# LDR_based_circuit.net
KiCad netlist of a schematic drawn in EAGLE
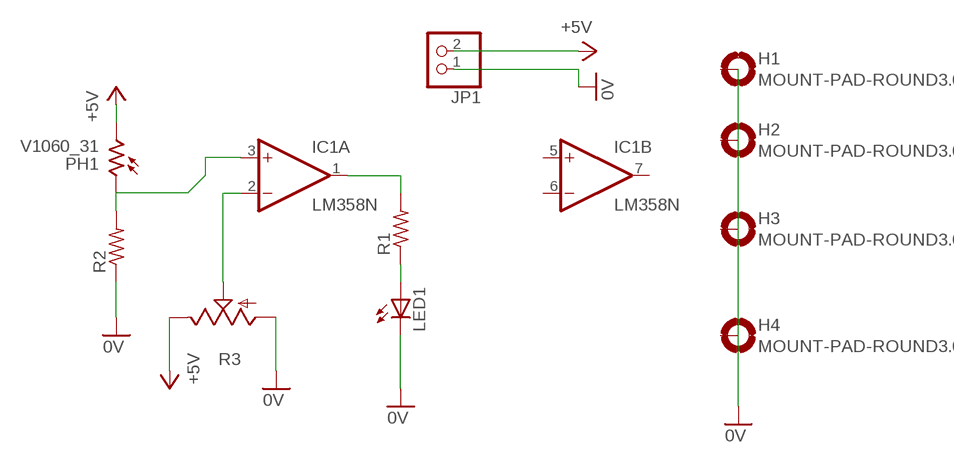
[diagram p0: schematic, sheet 1]

(export (version "E")
  (design (tool "Eeschema 10.0.6"))
  (components
    (comp (ref "H1")
      (value "MOUNT-PAD-ROUND3.0")
      (footprint "eagle-import:3,0-PAD")
      (libsource (lib "eagle-import") (part "MOUNT-PAD-ROUND3.0"))
    )
    (comp (ref "H2")
      (value "MOUNT-PAD-ROUND3.0")
      (footprint "eagle-import:3,0-PAD")
      (libsource (lib "eagle-import") (part "MOUNT-PAD-ROUND3.0"))
    )
    (comp (ref "H3")
      (value "MOUNT-PAD-ROUND3.0")
      (footprint "eagle-import:3,0-PAD")
      (libsource (lib "eagle-import") (part "MOUNT-PAD-ROUND3.0"))
    )
    (comp (ref "H4")
      (value "MOUNT-PAD-ROUND3.0")
      (footprint "eagle-import:3,0-PAD")
      (libsource (lib "eagle-import") (part "MOUNT-PAD-ROUND3.0"))
    )
    (comp (ref "IC1")
      (value "LM358N")
      (footprint "eagle-import:DIL08")
      (libsource (lib "eagle-import") (part "LM358N"))
    )
    (comp (ref "JP1")
      (value "PINHD-1X2")
      (footprint "eagle-import:1X02")
      (libsource (lib "eagle-import") (part "PINHD-1X2"))
    )
    (comp (ref "LED1")
      (value "LED5MM")
      (footprint "eagle-import:LED5MM")
      (libsource (lib "eagle-import") (part "LED5MM"))
    )
    (comp (ref "PH1")
      (value "V1060_31")
      (footprint "eagle-import:TO-5_V10")
      (libsource (lib "eagle-import") (part "?1060V_31"))
    )
    (comp (ref "R1")
      (value "R-US_0207/10")
      (footprint "eagle-import:0207_10")
      (libsource (lib "eagle-import") (part "R-US_0207/10"))
    )
    (comp (ref "R2")
      (value "R-US_0207/10")
      (footprint "eagle-import:0207_10")
      (libsource (lib "eagle-import") (part "R-US_0207/10"))
    )
    (comp (ref "R3")
      (value "TRIM_US-B25P")
      (footprint "eagle-import:B25P")
      (libsource (lib "eagle-import") (part "TRIM_US-B25P"))
    )
  )
  (nets
    (net (code "1") (name "+5V") (class "Default")
      (node (ref "JP1") (pin "2") (pinfunction "2_2") (pintype "passive"))
      (node (ref "PH1") (pin "2") (pinfunction "2_2") (pintype "passive"))
      (node (ref "R3") (pin "E") (pinfunction "E_E") (pintype "passive"))
    )
    (net (code "2") (name "0V") (class "Default")
      (node (ref "JP1") (pin "1") (pinfunction "1_1") (pintype "passive"))
      (node (ref "LED1") (pin "K") (pinfunction "C_K") (pintype "passive"))
      (node (ref "R2") (pin "1") (pinfunction "1_1") (pintype "passive"))
      (node (ref "R3") (pin "A") (pinfunction "A_A") (pintype "passive"))
    )
    (net (code "3") (name "Net-(IC1A-+IN)") (class "Default")
      (node (ref "IC1") (pin "3") (pinfunction "+IN_3") (pintype "input"))
      (node (ref "PH1") (pin "1") (pinfunction "1_1") (pintype "passive"))
      (node (ref "R2") (pin "2") (pinfunction "2_2") (pintype "passive"))
    )
    (net (code "4") (name "Net-(IC1A--IN)") (class "Default")
      (node (ref "IC1") (pin "2") (pinfunction "-IN_2") (pintype "input"))
      (node (ref "R3") (pin "S") (pinfunction "S_S") (pintype "passive"))
    )
    (net (code "5") (name "Net-(IC1A-OUT)") (class "Default")
      (node (ref "IC1") (pin "1") (pinfunction "OUT_1") (pintype "output"))
      (node (ref "R1") (pin "2") (pinfunction "2_2") (pintype "passive"))
    )
    (net (code "6") (name "Net-(LED1-PadA)") (class "Default")
      (node (ref "LED1") (pin "A") (pinfunction "A_A") (pintype "passive"))
      (node (ref "R1") (pin "1") (pinfunction "1_1") (pintype "passive"))
    )
    (net (code "7") (name "unconnected-(H1-MOUNT-PadB3,0)") (class "Default")
      (node (ref "H1") (pin "B3,0") (pinfunction "MOUNT_B3,0") (pintype "passive"))
    )
    (net (code "8") (name "unconnected-(H2-MOUNT-PadB3,0)") (class "Default")
      (node (ref "H2") (pin "B3,0") (pinfunction "MOUNT_B3,0") (pintype "passive"))
    )
    (net (code "9") (name "unconnected-(H3-MOUNT-PadB3,0)") (class "Default")
      (node (ref "H3") (pin "B3,0") (pinfunction "MOUNT_B3,0") (pintype "passive"))
    )
    (net (code "10") (name "unconnected-(H4-MOUNT-PadB3,0)") (class "Default")
      (node (ref "H4") (pin "B3,0") (pinfunction "MOUNT_B3,0") (pintype "passive"))
    )
    (net (code "11") (name "unconnected-(IC1B-+IN-Pad5)") (class "Default")
      (node (ref "IC1") (pin "5") (pinfunction "+IN_5") (pintype "input"))
    )
    (net (code "12") (name "unconnected-(IC1B--IN-Pad6)") (class "Default")
      (node (ref "IC1") (pin "6") (pinfunction "-IN_6") (pintype "input"))
    )
    (net (code "13") (name "unconnected-(IC1B-OUT-Pad7)") (class "Default")
      (node (ref "IC1") (pin "7") (pinfunction "OUT_7") (pintype "output"))
    )
  )
)
